# Full_Sonar_v1_opt_corrected_external_clo.net
KiCad netlist of a schematic drawn in EAGLE
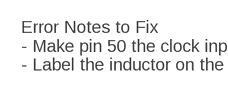
[diagram p0: schematic, sheet 1, part 1 of 2]
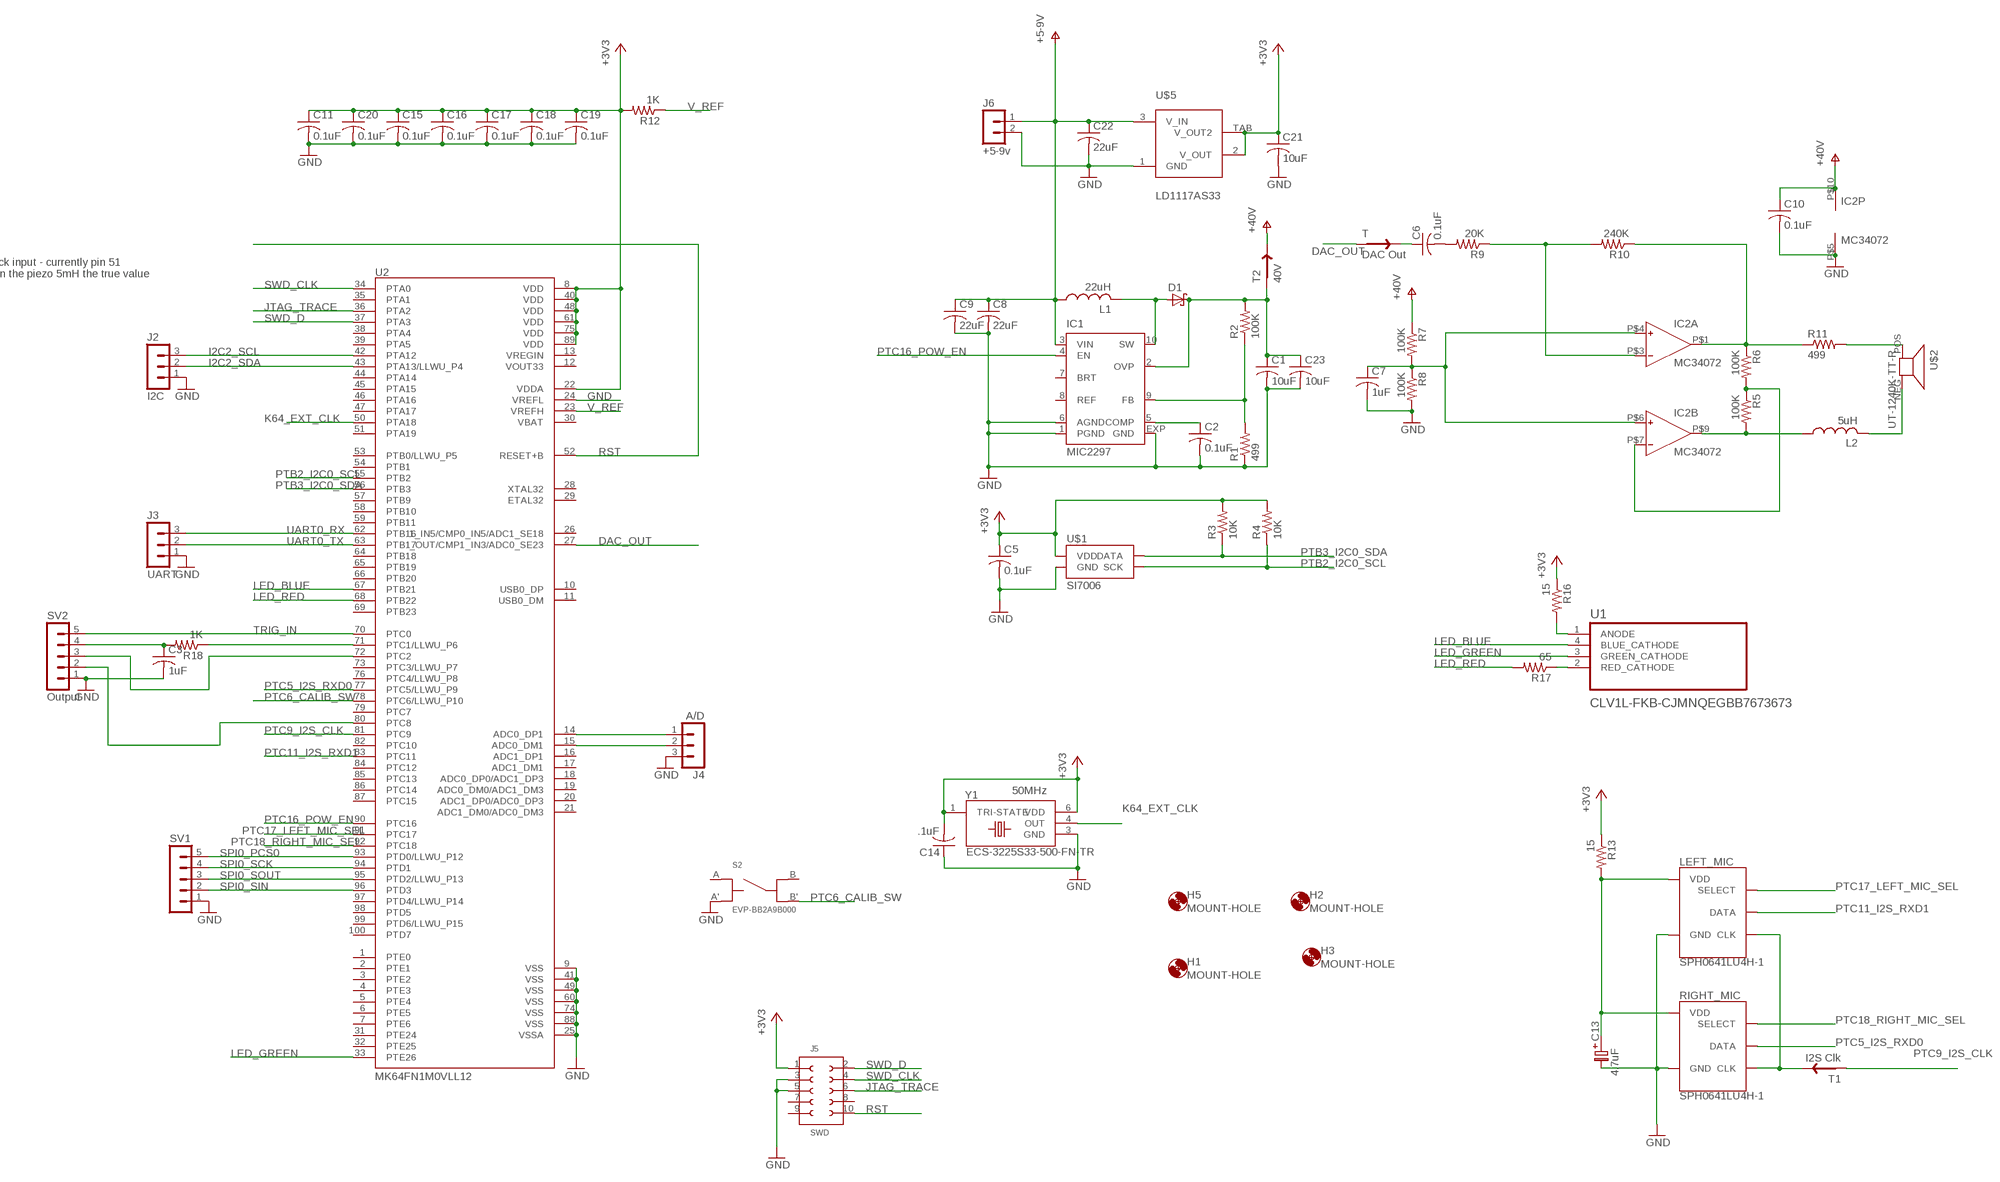
[diagram p1: schematic, sheet 1, part 2 of 2]

(export (version "E")
  (design (tool "Eeschema 10.0.6"))
  (components
    (comp (ref "C1")
      (value "10uF")
      (footprint "eagle-import:C1206")
      (libsource (lib "eagle-import") (part "C-USC1206"))
    )
    (comp (ref "C2")
      (value "0.1uF")
      (footprint "eagle-import:C0603")
      (libsource (lib "eagle-import") (part "C-USC0603"))
    )
    (comp (ref "C3")
      (value "1uF")
      (footprint "eagle-import:C0603")
      (libsource (lib "eagle-import") (part "C-USC0603"))
    )
    (comp (ref "C5")
      (value "0.1uF")
      (footprint "eagle-import:C0603")
      (libsource (lib "eagle-import") (part "C-USC0603"))
    )
    (comp (ref "C6")
      (value "0.1uF")
      (footprint "eagle-import:C0603")
      (libsource (lib "eagle-import") (part "C-USC0603"))
    )
    (comp (ref "C7")
      (value "1uF")
      (footprint "eagle-import:C0603")
      (libsource (lib "eagle-import") (part "C-USC0603"))
    )
    (comp (ref "C8")
      (value "22uF")
      (footprint "eagle-import:C0805")
      (libsource (lib "eagle-import") (part "C-USC0805"))
    )
    (comp (ref "C9")
      (value "22uF")
      (footprint "eagle-import:C0805")
      (libsource (lib "eagle-import") (part "C-USC0805"))
    )
    (comp (ref "C10")
      (value "0.1uF")
      (footprint "eagle-import:C0603")
      (libsource (lib "eagle-import") (part "C-USC0603"))
    )
    (comp (ref "C11")
      (value "0.1uF")
      (footprint "eagle-import:C0603")
      (libsource (lib "eagle-import") (part "C-USC0603"))
    )
    (comp (ref "C13")
      (value "4.7uF")
      (footprint "eagle-import:TE-A-3216")
      (libsource (lib "eagle-import") (part "CPOLA"))
    )
    (comp (ref "C14")
      (value ".1uF")
      (footprint "eagle-import:C0603")
      (libsource (lib "eagle-import") (part "C-USC0603"))
    )
    (comp (ref "C15")
      (value "0.1uF")
      (footprint "eagle-import:C0603K")
      (libsource (lib "eagle-import") (part "C-USC0603K"))
    )
    (comp (ref "C16")
      (value "0.1uF")
      (footprint "eagle-import:C0603")
      (libsource (lib "eagle-import") (part "C-USC0603"))
    )
    (comp (ref "C17")
      (value "0.1uF")
      (footprint "eagle-import:C0603")
      (libsource (lib "eagle-import") (part "C-USC0603"))
    )
    (comp (ref "C18")
      (value "0.1uF")
      (footprint "eagle-import:C0603")
      (libsource (lib "eagle-import") (part "C-USC0603"))
    )
    (comp (ref "C19")
      (value "0.1uF")
      (footprint "eagle-import:C0603")
      (libsource (lib "eagle-import") (part "C-USC0603"))
    )
    (comp (ref "C20")
      (value "0.1uF")
      (footprint "eagle-import:C0603K")
      (libsource (lib "eagle-import") (part "C-USC0603K"))
    )
    (comp (ref "C21")
      (value "10uF")
      (footprint "eagle-import:C0603")
      (libsource (lib "eagle-import") (part "C-USC0603"))
    )
    (comp (ref "C22")
      (value "22uF")
      (footprint "eagle-import:C0805")
      (libsource (lib "eagle-import") (part "C-USC0805"))
    )
    (comp (ref "C23")
      (value "10uF")
      (footprint "eagle-import:C1206")
      (libsource (lib "eagle-import") (part "C-USC1206"))
    )
    (comp (ref "D1")
      (value "DIODE_SCHOTTKYMICROSMP")
      (footprint "eagle-import:DIODE_SCHOTTKY_MICROSMP")
      (libsource (lib "eagle-import") (part "DIODE_SCHOTTKYMICROSMP"))
    )
    (comp (ref "H1")
      (value "MOUNT-HOLE")
      (footprint "eagle-import:SCREWHOLE2-56")
      (libsource (lib "eagle-import") (part "MOUNT-HOLE"))
    )
    (comp (ref "H2")
      (value "MOUNT-HOLE")
      (footprint "eagle-import:SCREWHOLE2-56")
      (libsource (lib "eagle-import") (part "MOUNT-HOLE"))
    )
    (comp (ref "H3")
      (value "MOUNT-HOLE")
      (footprint "eagle-import:SCREWHOLE2-56")
      (libsource (lib "eagle-import") (part "MOUNT-HOLE"))
    )
    (comp (ref "H5")
      (value "MOUNT-HOLE")
      (footprint "eagle-import:SCREWHOLE2-56")
      (libsource (lib "eagle-import") (part "MOUNT-HOLE"))
    )
    (comp (ref "IC1")
      (value "MIC2297")
      (footprint "eagle-import:MLF10")
      (fields (field (name "MPN") "MIC2297-38YML TR"))
      (libsource (lib "eagle-import") (part "MIC2297"))
    )
    (comp (ref "IC2")
      (value "MC34072")
      (footprint "eagle-import:WQFN10")
      (libsource (lib "eagle-import") (part "MC34072"))
    )
    (comp (ref "J2")
      (value "I2C")
      (footprint "eagle-import:MA03-1")
      (libsource (lib "eagle-import") (part "MA03-1"))
    )
    (comp (ref "J3")
      (value "UART")
      (footprint "eagle-import:MA03-1")
      (libsource (lib "eagle-import") (part "MA03-1"))
    )
    (comp (ref "J4")
      (value "A/D")
      (footprint "eagle-import:MA03-1")
      (libsource (lib "eagle-import") (part "MA03-1"))
    )
    (comp (ref "J5")
      (value "SWD")
      (footprint "eagle-import:62201021121")
      (fields (field (name "MF") "Würth Elektronik") (field (name "MP") "62201021121"))
      (libsource (lib "eagle-import") (part "62201021121"))
    )
    (comp (ref "J6")
      (value "+5-9v")
      (footprint "eagle-import:MA02-1")
      (libsource (lib "eagle-import") (part "MA02-1"))
    )
    (comp (ref "L1")
      (value "22uH")
      (footprint "eagle-import:INDUCTOR_BOURNS_SRN3012TA")
      (libsource (lib "eagle-import") (part "INDUCTOR7"))
    )
    (comp (ref "L2")
      (value "5uH")
      (footprint "eagle-import:INDUCTOR_BOURNS_SDR0503")
      (libsource (lib "eagle-import") (part "INDUCTOR"))
    )
    (comp (ref "LEFT_MIC")
      (value "SPH0641LU4H-1")
      (footprint "eagle-import:SPH0641LU4H-1")
      (libsource (lib "eagle-import") (part "SPH0641LU4H-1"))
    )
    (comp (ref "R1")
      (value "499")
      (footprint "eagle-import:R0603")
      (libsource (lib "eagle-import") (part "R-US_R0603"))
    )
    (comp (ref "R2")
      (value "100K")
      (footprint "eagle-import:R0603")
      (libsource (lib "eagle-import") (part "R-US_R0603"))
    )
    (comp (ref "R3")
      (value "10K")
      (footprint "eagle-import:R0603")
      (libsource (lib "eagle-import") (part "R-US_R0603"))
    )
    (comp (ref "R4")
      (value "10K")
      (footprint "eagle-import:R0603")
      (libsource (lib "eagle-import") (part "R-US_R0603"))
    )
    (comp (ref "R5")
      (value "100K")
      (footprint "eagle-import:R0603")
      (libsource (lib "eagle-import") (part "R-US_R0603"))
    )
    (comp (ref "R6")
      (value "100K")
      (footprint "eagle-import:R0603")
      (libsource (lib "eagle-import") (part "R-US_R0603"))
    )
    (comp (ref "R7")
      (value "100K")
      (footprint "eagle-import:R0603")
      (libsource (lib "eagle-import") (part "R-US_R0603"))
    )
    (comp (ref "R8")
      (value "100K")
      (footprint "eagle-import:R0603")
      (libsource (lib "eagle-import") (part "R-US_R0603"))
    )
    (comp (ref "R9")
      (value "20K")
      (footprint "eagle-import:R0603")
      (libsource (lib "eagle-import") (part "R-US_R0603"))
    )
    (comp (ref "R10")
      (value "240K")
      (footprint "eagle-import:R0603")
      (libsource (lib "eagle-import") (part "R-US_R0603"))
    )
    (comp (ref "R11")
      (value "499")
      (footprint "eagle-import:R0603")
      (libsource (lib "eagle-import") (part "R-US_R0603"))
    )
    (comp (ref "R12")
      (value "1K")
      (footprint "eagle-import:R0603")
      (libsource (lib "eagle-import") (part "R-US_R0603"))
    )
    (comp (ref "R13")
      (value "15")
      (footprint "eagle-import:R0603")
      (libsource (lib "eagle-import") (part "R-US_R0603"))
    )
    (comp (ref "R16")
      (value "15")
      (footprint "eagle-import:R0603")
      (libsource (lib "eagle-import") (part "R-US_R0603"))
    )
    (comp (ref "R17")
      (value "65")
      (footprint "eagle-import:R0603")
      (libsource (lib "eagle-import") (part "R-US_R0603"))
    )
    (comp (ref "R18")
      (value "1K")
      (footprint "eagle-import:R0603")
      (libsource (lib "eagle-import") (part "R-US_R0603"))
    )
    (comp (ref "RIGHT_MIC")
      (value "SPH0641LU4H-1")
      (footprint "eagle-import:SPH0641LU4H-1")
      (libsource (lib "eagle-import") (part "SPH0641LU4H-1"))
    )
    (comp (ref "S2")
      (value "EVP-BB2A9B000")
      (footprint "eagle-import:SW_EVP-BB2A9B000")
      (fields (field (name "MF") "Panasonic Electronic"))
      (libsource (lib "eagle-import") (part "EVP-BB2A9B000"))
    )
    (comp (ref "SV1")
      (value "MA05-1")
      (footprint "eagle-import:MA05-1")
      (libsource (lib "eagle-import") (part "MA05-1"))
    )
    (comp (ref "SV2")
      (value "Output")
      (footprint "eagle-import:MA05-1")
      (libsource (lib "eagle-import") (part "MA05-1"))
    )
    (comp (ref "T")
      (value "DAC Out")
      (footprint "eagle-import:TESTPAD")
      (libsource (lib "eagle-import") (part "TESTPAD{dblquote}{dblquote}"))
    )
    (comp (ref "T1")
      (value "I2S Clk")
      (footprint "eagle-import:TESTPAD")
      (libsource (lib "eagle-import") (part "TESTPAD{dblquote}{dblquote}"))
    )
    (comp (ref "T2")
      (value "40V")
      (footprint "eagle-import:TESTPAD")
      (libsource (lib "eagle-import") (part "TESTPAD{dblquote}{dblquote}"))
    )
    (comp (ref "U$1")
      (value "SI7006")
      (footprint "eagle-import:SI7006")
      (libsource (lib "eagle-import") (part "SI7006"))
    )
    (comp (ref "U$2")
      (value "UT-1240K-TT-R")
      (footprint "eagle-import:UT-1240K-TT-R")
      (libsource (lib "eagle-import") (part "UT-1240K-TT-R"))
    )
    (comp (ref "U$5")
      (value "LD1117AS33")
      (footprint "eagle-import:SOT223")
      (fields (field (name "MF") "STMicroelectronics"))
      (libsource (lib "eagle-import") (part "LD1117AS33"))
    )
    (comp (ref "U1")
      (value "CLV1L-FKB-CJMNQEGBB7673673")
      (footprint "eagle-import:SOJ150P350X372-4N")
      (fields (field (name "MF") "Cree"))
      (libsource (lib "eagle-import") (part "CLV1L-FKB-CJMNQEGBB7673673"))
    )
    (comp (ref "U2")
      (value "MK64FN1M0VLL12")
      (footprint "eagle-import:QFP50P1600X1600X170-100N")
      (fields (field (name "MF") "NXP Semiconductors"))
      (libsource (lib "eagle-import") (part "MK64FN1M0VLL12"))
    )
    (comp (ref "Y1")
      (value "ECS-3225S33-500-FN-TR")
      (footprint "eagle-import:XTAL_ECS-3225S18-050-EN-TR")
      (fields (field (name "DIGI-KEY_PART_NUMBER") "XC2226CT-ND") (field (name "MF") "ECS International"))
      (libsource (lib "eagle-import") (part "ECS-3225S33-500-FN-TR"))
    )
  )
  (nets
    (net (code "1") (name "+3V3") (class "Default")
      (node (ref "C11") (pin "1") (pinfunction "1_1") (pintype "passive"))
      (node (ref "C14") (pin "2") (pinfunction "2_2") (pintype "passive"))
      (node (ref "C15") (pin "1") (pinfunction "1_1") (pintype "passive"))
      (node (ref "C16") (pin "1") (pinfunction "1_1") (pintype "passive"))
      (node (ref "C17") (pin "1") (pinfunction "1_1") (pintype "passive"))
      (node (ref "C18") (pin "1") (pinfunction "1_1") (pintype "passive"))
      (node (ref "C19") (pin "1") (pinfunction "1_1") (pintype "passive"))
      (node (ref "C20") (pin "1") (pinfunction "1_1") (pintype "passive"))
      (node (ref "C21") (pin "1") (pinfunction "1_1") (pintype "passive"))
      (node (ref "C5") (pin "1") (pinfunction "1_1") (pintype "passive"))
      (node (ref "J5") (pin "1") (pinfunction "1_1") (pintype "passive"))
      (node (ref "R12") (pin "2") (pinfunction "2_2") (pintype "passive"))
      (node (ref "R13") (pin "1") (pinfunction "1_1") (pintype "passive"))
      (node (ref "R16") (pin "1") (pinfunction "1_1") (pintype "passive"))
      (node (ref "R3") (pin "2") (pinfunction "2_2") (pintype "passive"))
      (node (ref "R4") (pin "2") (pinfunction "2_2") (pintype "passive"))
      (node (ref "U$1") (pin "VDD") (pinfunction "VDD_VDD") (pintype "power_in"))
      (node (ref "U$5") (pin "2") (pinfunction "V_OUT_2") (pintype "bidirectional"))
      (node (ref "U$5") (pin "TAB") (pinfunction "V_OUT2_TAB") (pintype "bidirectional"))
      (node (ref "U2") (pin "22") (pinfunction "VDDA_22") (pintype "power_in"))
      (node (ref "U2") (pin "40") (pinfunction "VDD_40") (pintype "power_in"))
      (node (ref "U2") (pin "48") (pinfunction "VDD_48") (pintype "power_in"))
      (node (ref "U2") (pin "61") (pinfunction "VDD_61") (pintype "power_in"))
      (node (ref "U2") (pin "75") (pinfunction "VDD_75") (pintype "power_in"))
      (node (ref "U2") (pin "8") (pinfunction "VDD_8") (pintype "power_in"))
      (node (ref "U2") (pin "89") (pinfunction "VDD_89") (pintype "power_in"))
      (node (ref "Y1") (pin "1") (pinfunction "TRI-STATE_1") (pintype "input"))
      (node (ref "Y1") (pin "6") (pinfunction "VDD_6") (pintype "power_in"))
    )
    (net (code "2") (name "+5-9V") (class "Default")
      (node (ref "C22") (pin "1") (pinfunction "1_1") (pintype "passive"))
      (node (ref "C8") (pin "1") (pinfunction "1_1") (pintype "passive"))
      (node (ref "C9") (pin "1") (pinfunction "1_1") (pintype "passive"))
      (node (ref "IC1") (pin "3") (pinfunction "VIN_3") (pintype "input"))
      (node (ref "J6") (pin "1") (pinfunction "1_1") (pintype "passive"))
      (node (ref "L1") (pin "P$1") (pinfunction "1_P$1") (pintype "passive"))
      (node (ref "U$5") (pin "3") (pinfunction "V_IN_3") (pintype "bidirectional"))
    )
    (net (code "3") (name "DAC_OUT") (class "Default")
      (node (ref "T") (pin "IN") (pinfunction "IN_IN") (pintype "passive"))
      (node (ref "U2") (pin "27") (pinfunction "_OUT/CMP1_IN3/ADC0_SE23_27") (pintype "bidirectional"))
    )
    (net (code "4") (name "GND") (class "Default")
      (node (ref "C1") (pin "2") (pinfunction "2_2") (pintype "passive"))
      (node (ref "C10") (pin "2") (pinfunction "2_2") (pintype "passive"))
      (node (ref "C11") (pin "2") (pinfunction "2_2") (pintype "passive"))
      (node (ref "C13") (pin "-") (pinfunction "-_-") (pintype "passive"))
      (node (ref "C14") (pin "1") (pinfunction "1_1") (pintype "passive"))
      (node (ref "C15") (pin "2") (pinfunction "2_2") (pintype "passive"))
      (node (ref "C16") (pin "2") (pinfunction "2_2") (pintype "passive"))
      (node (ref "C17") (pin "2") (pinfunction "2_2") (pintype "passive"))
      (node (ref "C18") (pin "2") (pinfunction "2_2") (pintype "passive"))
      (node (ref "C19") (pin "2") (pinfunction "2_2") (pintype "passive"))
      (node (ref "C2") (pin "2") (pinfunction "2_2") (pintype "passive"))
      (node (ref "C20") (pin "2") (pinfunction "2_2") (pintype "passive"))
      (node (ref "C21") (pin "2") (pinfunction "2_2") (pintype "passive"))
      (node (ref "C22") (pin "2") (pinfunction "2_2") (pintype "passive"))
      (node (ref "C23") (pin "2") (pinfunction "2_2") (pintype "passive"))
      (node (ref "C3") (pin "2") (pinfunction "2_2") (pintype "passive"))
      (node (ref "C5") (pin "2") (pinfunction "2_2") (pintype "passive"))
      (node (ref "C7") (pin "2") (pinfunction "2_2") (pintype "passive"))
      (node (ref "C8") (pin "2") (pinfunction "2_2") (pintype "passive"))
      (node (ref "C9") (pin "2") (pinfunction "2_2") (pintype "passive"))
      (node (ref "IC1") (pin "1") (pinfunction "PGND_1") (pintype "input"))
      (node (ref "IC1") (pin "6") (pinfunction "AGND_6") (pintype "input"))
      (node (ref "IC1") (pin "EXP") (pinfunction "GND_EXP") (pintype "input"))
      (node (ref "IC2") (pin "P$5") (pinfunction "V-_P$5") (pintype "power_in"))
      (node (ref "J2") (pin "1") (pinfunction "1_1") (pintype "passive"))
      (node (ref "J3") (pin "1") (pinfunction "1_1") (pintype "passive"))
      (node (ref "J4") (pin "3") (pinfunction "3_3") (pintype "passive"))
      (node (ref "J5") (pin "3") (pinfunction "2_3") (pintype "passive"))
      (node (ref "J5") (pin "5") (pinfunction "3_5") (pintype "passive"))
      (node (ref "J6") (pin "2") (pinfunction "2_2") (pintype "passive"))
      (node (ref "LEFT_MIC") (pin "3") (pinfunction "GND_3") (pintype "bidirectional"))
      (node (ref "R1") (pin "1") (pinfunction "1_1") (pintype "passive"))
      (node (ref "R8") (pin "2") (pinfunction "2_2") (pintype "passive"))
      (node (ref "RIGHT_MIC") (pin "3") (pinfunction "GND_3") (pintype "bidirectional"))
      (node (ref "S2") (pin "A'") (pinfunction "A'_A'") (pintype "passive"))
      (node (ref "SV1") (pin "1") (pinfunction "1_1") (pintype "passive"))
      (node (ref "SV2") (pin "1") (pinfunction "1_1") (pintype "passive"))
      (node (ref "U$1") (pin "GND") (pinfunction "GND_GND") (pintype "power_in"))
      (node (ref "U$5") (pin "1") (pinfunction "GND_1") (pintype "bidirectional"))
      (node (ref "U2") (pin "24") (pinfunction "VREFL_24") (pintype "power_in"))
      (node (ref "U2") (pin "25") (pinfunction "VSSA_25") (pintype "power_in"))
      (node (ref "U2") (pin "41") (pinfunction "VSS_41") (pintype "power_in"))
      (node (ref "U2") (pin "49") (pinfunction "VSS_49") (pintype "power_in"))
      (node (ref "U2") (pin "60") (pinfunction "VSS_60") (pintype "power_in"))
      (node (ref "U2") (pin "74") (pinfunction "VSS_74") (pintype "power_in"))
      (node (ref "U2") (pin "88") (pinfunction "VSS_88") (pintype "power_in"))
      (node (ref "U2") (pin "9") (pinfunction "VSS_9") (pintype "power_in"))
      (node (ref "Y1") (pin "3") (pinfunction "GND_3") (pintype "power_in"))
    )
    (net (code "5") (name "I2C2_SCL") (class "Default")
      (node (ref "J2") (pin "3") (pinfunction "3_3") (pintype "passive"))
      (node (ref "U2") (pin "42") (pinfunction "PTA12_42") (pintype "bidirectional"))
    )
    (net (code "6") (name "I2C2_SDA") (class "Default")
      (node (ref "J2") (pin "2") (pinfunction "2_2") (pintype "passive"))
      (node (ref "U2") (pin "43") (pinfunction "PTA13/LLWU_P4_43") (pintype "bidirectional"))
    )
    (net (code "7") (name "JTAG_TRACE") (class "Default")
      (node (ref "J5") (pin "6") (pinfunction "8_6") (pintype "passive"))
      (node (ref "U2") (pin "36") (pinfunction "PTA2_36") (pintype "bidirectional"))
    )
    (net (code "8") (name "K64_EXT_CLK") (class "Default")
      (node (ref "U2") (pin "50") (pinfunction "PTA18_50") (pintype "bidirectional"))
      (node (ref "Y1") (pin "4") (pinfunction "OUT_4") (pintype "output"))
    )
    (net (code "9") (name "LED_BLUE") (class "Default")
      (node (ref "U1") (pin "4") (pinfunction "BLUE_CATHODE_4") (pintype "bidirectional"))
      (node (ref "U2") (pin "67") (pinfunction "PTB21_67") (pintype "bidirectional"))
    )
    (net (code "10") (name "LED_GREEN") (class "Default")
      (node (ref "U1") (pin "3") (pinfunction "GREEN_CATHODE_3") (pintype "bidirectional"))
      (node (ref "U2") (pin "33") (pinfunction "PTE26_33") (pintype "bidirectional"))
    )
    (net (code "11") (name "LED_RED") (class "Default")
      (node (ref "R17") (pin "2") (pinfunction "2_2") (pintype "passive"))
      (node (ref "U2") (pin "68") (pinfunction "PTB22_68") (pintype "bidirectional"))
    )
    (net (code "12") (name "Net-(C3-Pad1)") (class "Default")
      (node (ref "C3") (pin "1") (pinfunction "1_1") (pintype "passive"))
      (node (ref "R18") (pin "2") (pinfunction "2_2") (pintype "passive"))
      (node (ref "SV2") (pin "4") (pinfunction "4_4") (pintype "passive"))
    )
    (net (code "13") (name "Net-(C6-Pad1)") (class "Default")
      (node (ref "C6") (pin "1") (pinfunction "1_1") (pintype "passive"))
      (node (ref "T") (pin "OUT") (pinfunction "OUT_OUT") (pintype "passive"))
    )
    (net (code "14") (name "Net-(C6-Pad2)") (class "Default")
      (node (ref "C6") (pin "2") (pinfunction "2_2") (pintype "passive"))
      (node (ref "R9") (pin "2") (pinfunction "2_2") (pintype "passive"))
    )
    (net (code "15") (name "Net-(IC1-COMP)") (class "Default")
      (node (ref "C2") (pin "1") (pinfunction "1_1") (pintype "passive"))
      (node (ref "IC1") (pin "5") (pinfunction "COMP_5") (pintype "passive"))
    )
    (net (code "16") (name "Net-(IC1-FB)") (class "Default")
      (node (ref "IC1") (pin "9") (pinfunction "FB_9") (pintype "input"))
      (node (ref "R1") (pin "2") (pinfunction "2_2") (pintype "passive"))
      (node (ref "R2") (pin "1") (pinfunction "1_1") (pintype "passive"))
    )
    (net (code "17") (name "Net-(IC1-OVP)") (class "Default")
      (node (ref "C1") (pin "1") (pinfunction "1_1") (pintype "passive"))
      (node (ref "C23") (pin "1") (pinfunction "1_1") (pintype "passive"))
      (node (ref "D1") (pin "C") (pinfunction "C_C") (pintype "passive"))
      (node (ref "IC1") (pin "2") (pinfunction "OVP_2") (pintype "input"))
      (node (ref "R2") (pin "2") (pinfunction "2_2") (pintype "passive"))
      (node (ref "T2") (pin "IN") (pinfunction "IN_IN") (pintype "passive"))
    )
    (net (code "18") (name "Net-(IC1-SW)") (class "Default")
      (node (ref "D1") (pin "A") (pinfunction "A_A") (pintype "passive"))
      (node (ref "IC1") (pin "10") (pinfunction "SW_10") (pintype "open_collector"))
      (node (ref "L1") (pin "P$2") (pinfunction "2_P$2") (pintype "passive"))
    )
    (net (code "19") (name "Net-(IC2A-IN+)") (class "Default")
      (node (ref "C7") (pin "1") (pinfunction "1_1") (pintype "passive"))
      (node (ref "IC2") (pin "P$4") (pinfunction "IN+_P$4") (pintype "input"))
      (node (ref "IC2") (pin "P$6") (pinfunction "IN+_P$6") (pintype "input"))
      (node (ref "R7") (pin "2") (pinfunction "2_2") (pintype "passive"))
      (node (ref "R8") (pin "1") (pinfunction "1_1") (pintype "passive"))
    )
    (net (code "20") (name "Net-(IC2A-IN-)") (class "Default")
      (node (ref "IC2") (pin "P$3") (pinfunction "IN-_P$3") (pintype "input"))
      (node (ref "R10") (pin "2") (pinfunction "2_2") (pintype "passive"))
      (node (ref "R9") (pin "1") (pinfunction "1_1") (pintype "passive"))
    )
    (net (code "21") (name "Net-(IC2A-OUT)") (class "Default")
      (node (ref "IC2") (pin "P$1") (pinfunction "OUT_P$1") (pintype "output"))
      (node (ref "R10") (pin "1") (pinfunction "1_1") (pintype "passive"))
      (node (ref "R11") (pin "1") (pinfunction "1_1") (pintype "passive"))
      (node (ref "R6") (pin "1") (pinfunction "1_1") (pintype "passive"))
    )
    (net (code "22") (name "Net-(IC2B-IN-)") (class "Default")
      (node (ref "IC2") (pin "P$7") (pinfunction "IN-_P$7") (pintype "input"))
      (node (ref "R5") (pin "1") (pinfunction "1_1") (pintype "passive"))
      (node (ref "R6") (pin "2") (pinfunction "2_2") (pintype "passive"))
    )
    (net (code "23") (name "Net-(IC2B-OUT)") (class "Default")
      (node (ref "IC2") (pin "P$9") (pinfunction "OUT_P$9") (pintype "output"))
      (node (ref "L2") (pin "1") (pinfunction "1_1") (pintype "passive"))
      (node (ref "R5") (pin "2") (pinfunction "2_2") (pintype "passive"))
    )
    (net (code "24") (name "Net-(L2-Pad2)") (class "Default")
      (node (ref "L2") (pin "2") (pinfunction "2_2") (pintype "passive"))
      (node (ref "U$2") (pin "NEG") (pinfunction "NEG_NEG") (pintype "passive"))
    )
    (net (code "25") (name "Net-(LEFT_MIC-CLK)") (class "Default")
      (node (ref "LEFT_MIC") (pin "4") (pinfunction "CLK_4") (pintype "bidirectional"))
      (node (ref "RIGHT_MIC") (pin "4") (pinfunction "CLK_4") (pintype "bidirectional"))
      (node (ref "T1") (pin "OUT") (pinfunction "OUT_OUT") (pintype "passive"))
    )
    (net (code "26") (name "Net-(LEFT_MIC-VDD)") (class "Default")
      (node (ref "C13") (pin "+") (pinfunction "+_+") (pintype "passive"))
      (node (ref "LEFT_MIC") (pin "5") (pinfunction "VDD_5") (pintype "bidirectional"))
      (node (ref "R13") (pin "2") (pinfunction "2_2") (pintype "passive"))
      (node (ref "RIGHT_MIC") (pin "5") (pinfunction "VDD_5") (pintype "bidirectional"))
    )
    (net (code "27") (name "Net-(R11-Pad2)") (class "Default")
      (node (ref "R11") (pin "2") (pinfunction "2_2") (pintype "passive"))
      (node (ref "U$2") (pin "POS") (pinfunction "POS_POS") (pintype "passive"))
    )
    (net (code "28") (name "Net-(U1-ANODE)") (class "Default")
      (node (ref "R16") (pin "2") (pinfunction "2_2") (pintype "passive"))
      (node (ref "U1") (pin "1") (pinfunction "ANODE_1") (pintype "bidirectional"))
    )
    (net (code "29") (name "Net-(U1-RED_CATHODE)") (class "Default")
      (node (ref "R17") (pin "1") (pinfunction "1_1") (pintype "passive"))
      (node (ref "U1") (pin "2") (pinfunction "RED_CATHODE_2") (pintype "bidirectional"))
    )
    (net (code "30") (name "Net-(U2-ADC0_DM1)") (class "Default")
      (node (ref "J4") (pin "2") (pinfunction "2_2") (pintype "passive"))
      (node (ref "U2") (pin "15") (pinfunction "ADC0_DM1_15") (pintype "bidirectional"))
    )
    (net (code "31") (name "Net-(U2-ADC0_DP1)") (class "Default")
      (node (ref "J4") (pin "1") (pinfunction "1_1") (pintype "passive"))
      (node (ref "U2") (pin "14") (pinfunction "ADC0_DP1_14") (pintype "bidirectional"))
    )
    (net (code "32") (name "Net-(U2-PTC1{slash}LLWU_P6)") (class "Default")
      (node (ref "R18") (pin "1") (pinfunction "1_1") (pintype "passive"))
      (node (ref "U2") (pin "71") (pinfunction "PTC1/LLWU_P6_71") (pintype "bidirectional"))
    )
    (net (code "33") (name "Net-(U2-PTC2)") (class "Default")
      (node (ref "SV2") (pin "3") (pinfunction "3_3") (pintype "passive"))
      (node (ref "U2") (pin "72") (pinfunction "PTC2_72") (pintype "bidirectional"))
    )
    (net (code "34") (name "Net-(U2-PTC8)") (class "Default")
      (node (ref "SV2") (pin "2") (pinfunction "2_2") (pintype "passive"))
      (node (ref "U2") (pin "80") (pinfunction "PTC8_80") (pintype "bidirectional"))
    )
    (net (code "35") (name "PTB2_I2C0_SCL") (class "Default")
      (node (ref "R4") (pin "1") (pinfunction "1_1") (pintype "passive"))
      (node (ref "U$1") (pin "SCK") (pinfunction "SCK_SCK") (pintype "input"))
      (node (ref "U2") (pin "55") (pinfunction "PTB2_55") (pintype "bidirectional"))
    )
    (net (code "36") (name "PTB3_I2C0_SDA") (class "Default")
      (node (ref "R3") (pin "1") (pinfunction "1_1") (pintype "passive"))
      (node (ref "U$1") (pin "DATA") (pinfunction "DATA_DATA") (pintype "bidirectional"))
      (node (ref "U2") (pin "56") (pinfunction "PTB3_56") (pintype "bidirectional"))
    )
    (net (code "37") (name "PTC5_I2S_RXD0") (class "Default")
      (node (ref "RIGHT_MIC") (pin "1") (pinfunction "DATA_1") (pintype "bidirectional"))
      (node (ref "U2") (pin "77") (pinfunction "PTC5/LLWU_P9_77") (pintype "bidirectional"))
    )
    (net (code "38") (name "PTC6_CALIB_SW") (class "Default")
      (node (ref "S2") (pin "B'") (pinfunction "B'_B'") (pintype "passive"))
      (node (ref "U2") (pin "78") (pinfunction "PTC6/LLWU_P10_78") (pintype "bidirectional"))
    )
    (net (code "39") (name "PTC9_I2S_CLK") (class "Default")
      (node (ref "T1") (pin "IN") (pinfunction "IN_IN") (pintype "passive"))
      (node (ref "U2") (pin "81") (pinfunction "PTC9_81") (pintype "bidirectional"))
    )
    (net (code "40") (name "PTC11_I2S_RXD1") (class "Default")
      (node (ref "LEFT_MIC") (pin "1") (pinfunction "DATA_1") (pintype "bidirectional"))
      (node (ref "U2") (pin "83") (pinfunction "PTC11_83") (pintype "bidirectional"))
    )
    (net (code "41") (name "PTC16_POW_EN") (class "Default")
      (node (ref "IC1") (pin "4") (pinfunction "EN_4") (pintype "input"))
      (node (ref "U2") (pin "90") (pinfunction "PTC16_90") (pintype "bidirectional"))
    )
    (net (code "42") (name "PTC17_LEFT_MIC_SEL") (class "Default")
      (node (ref "LEFT_MIC") (pin "2") (pinfunction "SELECT_2") (pintype "bidirectional"))
      (node (ref "U2") (pin "91") (pinfunction "PTC17_91") (pintype "bidirectional"))
    )
    (net (code "43") (name "PTC18_RIGHT_MIC_SEL") (class "Default")
      (node (ref "RIGHT_MIC") (pin "2") (pinfunction "SELECT_2") (pintype "bidirectional"))
      (node (ref "U2") (pin "92") (pinfunction "PTC18_92") (pintype "bidirectional"))
    )
    (net (code "44") (name "RST") (class "Default")
      (node (ref "J5") (pin "10") (pinfunction "6_10") (pintype "passive"))
      (node (ref "U2") (pin "52") (pinfunction "RESET+B_52") (pintype "bidirectional"))
    )
    (net (code "45") (name "SPI0_PCS0") (class "Default")
      (node (ref "SV1") (pin "5") (pinfunction "5_5") (pintype "passive"))
      (node (ref "U2") (pin "93") (pinfunction "PTD0/LLWU_P12_93") (pintype "bidirectional"))
    )
    (net (code "46") (name "SPI0_SCK") (class "Default")
      (node (ref "SV1") (pin "4") (pinfunction "4_4") (pintype "passive"))
      (node (ref "U2") (pin "94") (pinfunction "PTD1_94") (pintype "bidirectional"))
    )
    (net (code "47") (name "SPI0_SIN") (class "Default")
      (node (ref "SV1") (pin "2") (pinfunction "2_2") (pintype "passive"))
      (node (ref "U2") (pin "96") (pinfunction "PTD3_96") (pintype "bidirectional"))
    )
    (net (code "48") (name "SPI0_SOUT") (class "Default")
      (node (ref "SV1") (pin "3") (pinfunction "3_3") (pintype "passive"))
      (node (ref "U2") (pin "95") (pinfunction "PTD2/LLWU_P13_95") (pintype "bidirectional"))
    )
    (net (code "49") (name "SWD_CLK") (class "Default")
      (node (ref "J5") (pin "4") (pinfunction "9_4") (pintype "passive"))
      (node (ref "U2") (pin "34") (pinfunction "PTA0_34") (pintype "bidirectional"))
    )
    (net (code "50") (name "SWD_D") (class "Default")
      (node (ref "J5") (pin "2") (pinfunction "10_2") (pintype "passive"))
      (node (ref "U2") (pin "37") (pinfunction "PTA3_37") (pintype "bidirectional"))
    )
    (net (code "51") (name "TRIG_IN") (class "Default")
      (node (ref "SV2") (pin "5") (pinfunction "5_5") (pintype "passive"))
      (node (ref "U2") (pin "70") (pinfunction "PTC0_70") (pintype "bidirectional"))
    )
    (net (code "52") (name "UART0_RX") (class "Default")
      (node (ref "J3") (pin "3") (pinfunction "3_3") (pintype "passive"))
      (node (ref "U2") (pin "62") (pinfunction "PTB16_62") (pintype "bidirectional"))
    )
    (net (code "53") (name "UART0_TX") (class "Default")
      (node (ref "J3") (pin "2") (pinfunction "2_2") (pintype "passive"))
      (node (ref "U2") (pin "63") (pinfunction "PTB17_63") (pintype "bidirectional"))
    )
    (net (code "54") (name "V+") (class "Default")
      (node (ref "C10") (pin "1") (pinfunction "1_1") (pintype "passive"))
      (node (ref "IC2") (pin "P$10") (pinfunction "V+_P$10") (pintype "power_in"))
      (node (ref "R7") (pin "1") (pinfunction "1_1") (pintype "passive"))
      (node (ref "T2") (pin "OUT") (pinfunction "OUT_OUT") (pintype "passive"))
    )
    (net (code "55") (name "VBAT") (class "Default")
      (node (ref "U2") (pin "30") (pinfunction "VBAT_30") (pintype "power_in"))
    )
    (net (code "56") (name "VOUT33") (class "Default")
      (node (ref "U2") (pin "12") (pinfunction "VOUT33_12") (pintype "power_in"))
    )
    (net (code "57") (name "VREGIN") (class "Default")
      (node (ref "U2") (pin "13") (pinfunction "VREGIN_13") (pintype "power_in"))
    )
    (net (code "58") (name "V_REF") (class "Default")
      (node (ref "R12") (pin "1") (pinfunction "1_1") (pintype "passive"))
      (node (ref "U2") (pin "23") (pinfunction "VREFH_23") (pintype "power_in"))
    )
    (net (code "59") (name "unconnected-(IC1-BRT-Pad7)") (class "Default")
      (node (ref "IC1") (pin "7") (pinfunction "BRT_7") (pintype "input"))
    )
    (net (code "60") (name "unconnected-(IC1-REF-Pad8)") (class "Default")
      (node (ref "IC1") (pin "8") (pinfunction "REF_8") (pintype "input"))
    )
    (net (code "61") (name "unconnected-(J5-4-Pad7)") (class "Default")
      (node (ref "J5") (pin "7") (pinfunction "4_7") (pintype "passive"))
    )
    (net (code "62") (name "unconnected-(J5-5-Pad9)") (class "Default")
      (node (ref "J5") (pin "9") (pinfunction "5_9") (pintype "passive"))
    )
    (net (code "63") (name "unconnected-(J5-7-Pad8)") (class "Default")
      (node (ref "J5") (pin "8") (pinfunction "7_8") (pintype "passive"))
    )
    (net (code "64") (name "unconnected-(S2-PadA)") (class "Default")
      (node (ref "S2") (pin "A") (pinfunction "A_A") (pintype "passive"))
    )
    (net (code "65") (name "unconnected-(S2-PadB)") (class "Default")
      (node (ref "S2") (pin "B") (pinfunction "B_B") (pintype "passive"))
    )
    (net (code "66") (name "unconnected-(U2-1_IN5{slash}CMP0_IN5{slash}ADC1_SE18-Pad26)") (class "Default")
      (node (ref "U2") (pin "26") (pinfunction "1_IN5/CMP0_IN5/ADC1_SE18_26") (pintype "bidirectional"))
    )
    (net (code "67") (name "unconnected-(U2-ADC0_DM0{slash}ADC1_DM3-Pad19)") (class "Default")
      (node (ref "U2") (pin "19") (pinfunction "ADC0_DM0/ADC1_DM3_19") (pintype "bidirectional"))
    )
    (net (code "68") (name "unconnected-(U2-ADC0_DP0{slash}ADC1_DP3-Pad18)") (class "Default")
      (node (ref "U2") (pin "18") (pinfunction "ADC0_DP0/ADC1_DP3_18") (pintype "bidirectional"))
    )
    (net (code "69") (name "unconnected-(U2-ADC1_DM0{slash}ADC0_DM3-Pad21)") (class "Default")
      (node (ref "U2") (pin "21") (pinfunction "ADC1_DM0/ADC0_DM3_21") (pintype "bidirectional"))
    )
    (net (code "70") (name "unconnected-(U2-ADC1_DM1-Pad17)") (class "Default")
      (node (ref "U2") (pin "17") (pinfunction "ADC1_DM1_17") (pintype "bidirectional"))
    )
    (net (code "71") (name "unconnected-(U2-ADC1_DP0{slash}ADC0_DP3-Pad20)") (class "Default")
      (node (ref "U2") (pin "20") (pinfunction "ADC1_DP0/ADC0_DP3_20") (pintype "bidirectional"))
    )
    (net (code "72") (name "unconnected-(U2-ADC1_DP1-Pad16)") (class "Default")
      (node (ref "U2") (pin "16") (pinfunction "ADC1_DP1_16") (pintype "bidirectional"))
    )
    (net (code "73") (name "unconnected-(U2-ETAL32-Pad29)") (class "Default")
      (node (ref "U2") (pin "29") (pinfunction "ETAL32_29") (pintype "bidirectional"))
    )
    (net (code "74") (name "unconnected-(U2-PTA1-Pad35)") (class "Default")
      (node (ref "U2") (pin "35") (pinfunction "PTA1_35") (pintype "bidirectional"))
    )
    (net (code "75") (name "unconnected-(U2-PTA4-Pad38)") (class "Default")
      (node (ref "U2") (pin "38") (pinfunction "PTA4_38") (pintype "bidirectional"))
    )
    (net (code "76") (name "unconnected-(U2-PTA5-Pad39)") (class "Default")
      (node (ref "U2") (pin "39") (pinfunction "PTA5_39") (pintype "bidirectional"))
    )
    (net (code "77") (name "unconnected-(U2-PTA14-Pad44)") (class "Default")
      (node (ref "U2") (pin "44") (pinfunction "PTA14_44") (pintype "bidirectional"))
    )
    (net (code "78") (name "unconnected-(U2-PTA15-Pad45)") (class "Default")
      (node (ref "U2") (pin "45") (pinfunction "PTA15_45") (pintype "bidirectional"))
    )
    (net (code "79") (name "unconnected-(U2-PTA16-Pad46)") (class "Default")
      (node (ref "U2") (pin "46") (pinfunction "PTA16_46") (pintype "bidirectional"))
    )
    (net (code "80") (name "unconnected-(U2-PTA17-Pad47)") (class "Default")
      (node (ref "U2") (pin "47") (pinfunction "PTA17_47") (pintype "bidirectional"))
    )
    (net (code "81") (name "unconnected-(U2-PTA19-Pad51)") (class "Default")
      (node (ref "U2") (pin "51") (pinfunction "PTA19_51") (pintype "bidirectional"))
    )
    (net (code "82") (name "unconnected-(U2-PTB0{slash}LLWU_P5-Pad53)") (class "Default")
      (node (ref "U2") (pin "53") (pinfunction "PTB0/LLWU_P5_53") (pintype "bidirectional"))
    )
    (net (code "83") (name "unconnected-(U2-PTB1-Pad54)") (class "Default")
      (node (ref "U2") (pin "54") (pinfunction "PTB1_54") (pintype "bidirectional"))
    )
    (net (code "84") (name "unconnected-(U2-PTB9-Pad57)") (class "Default")
      (node (ref "U2") (pin "57") (pinfunction "PTB9_57") (pintype "bidirectional"))
    )
    (net (code "85") (name "unconnected-(U2-PTB10-Pad58)") (class "Default")
      (node (ref "U2") (pin "58") (pinfunction "PTB10_58") (pintype "bidirectional"))
    )
    (net (code "86") (name "unconnected-(U2-PTB11-Pad59)") (class "Default")
      (node (ref "U2") (pin "59") (pinfunction "PTB11_59") (pintype "bidirectional"))
    )
    (net (code "87") (name "unconnected-(U2-PTB18-Pad64)") (class "Default")
      (node (ref "U2") (pin "64") (pinfunction "PTB18_64") (pintype "bidirectional"))
    )
    (net (code "88") (name "unconnected-(U2-PTB19-Pad65)") (class "Default")
      (node (ref "U2") (pin "65") (pinfunction "PTB19_65") (pintype "bidirectional"))
    )
    (net (code "89") (name "unconnected-(U2-PTB20-Pad66)") (class "Default")
      (node (ref "U2") (pin "66") (pinfunction "PTB20_66") (pintype "bidirectional"))
    )
    (net (code "90") (name "unconnected-(U2-PTB23-Pad69)") (class "Default")
      (node (ref "U2") (pin "69") (pinfunction "PTB23_69") (pintype "bidirectional"))
    )
    (net (code "91") (name "unconnected-(U2-PTC3{slash}LLWU_P7-Pad73)") (class "Default")
      (node (ref "U2") (pin "73") (pinfunction "PTC3/LLWU_P7_73") (pintype "bidirectional"))
    )
    (net (code "92") (name "unconnected-(U2-PTC4{slash}LLWU_P8-Pad76)") (class "Default")
      (node (ref "U2") (pin "76") (pinfunction "PTC4/LLWU_P8_76") (pintype "bidirectional"))
    )
    (net (code "93") (name "unconnected-(U2-PTC7-Pad79)") (class "Default")
      (node (ref "U2") (pin "79") (pinfunction "PTC7_79") (pintype "bidirectional"))
    )
    (net (code "94") (name "unconnected-(U2-PTC10-Pad82)") (class "Default")
      (node (ref "U2") (pin "82") (pinfunction "PTC10_82") (pintype "bidirectional"))
    )
    (net (code "95") (name "unconnected-(U2-PTC12-Pad84)") (class "Default")
      (node (ref "U2") (pin "84") (pinfunction "PTC12_84") (pintype "bidirectional"))
    )
    (net (code "96") (name "unconnected-(U2-PTC13-Pad85)") (class "Default")
      (node (ref "U2") (pin "85") (pinfunction "PTC13_85") (pintype "bidirectional"))
    )
    (net (code "97") (name "unconnected-(U2-PTC14-Pad86)") (class "Default")
      (node (ref "U2") (pin "86") (pinfunction "PTC14_86") (pintype "bidirectional"))
    )
    (net (code "98") (name "unconnected-(U2-PTC15-Pad87)") (class "Default")
      (node (ref "U2") (pin "87") (pinfunction "PTC15_87") (pintype "bidirectional"))
    )
    (net (code "99") (name "unconnected-(U2-PTD4{slash}LLWU_P14-Pad97)") (class "Default")
      (node (ref "U2") (pin "97") (pinfunction "PTD4/LLWU_P14_97") (pintype "bidirectional"))
    )
    (net (code "100") (name "unconnected-(U2-PTD5-Pad98)") (class "Default")
      (node (ref "U2") (pin "98") (pinfunction "PTD5_98") (pintype "bidirectional"))
    )
    (net (code "101") (name "unconnected-(U2-PTD6{slash}LLWU_P15-Pad99)") (class "Default")
      (node (ref "U2") (pin "99") (pinfunction "PTD6/LLWU_P15_99") (pintype "bidirectional"))
    )
    (net (code "102") (name "unconnected-(U2-PTD7-Pad100)") (class "Default")
      (node (ref "U2") (pin "100") (pinfunction "PTD7_100") (pintype "bidirectional"))
    )
    (net (code "103") (name "unconnected-(U2-PTE0-Pad1)") (class "Default")
      (node (ref "U2") (pin "1") (pinfunction "PTE0_1") (pintype "bidirectional"))
    )
    (net (code "104") (name "unconnected-(U2-PTE1-Pad2)") (class "Default")
      (node (ref "U2") (pin "2") (pinfunction "PTE1_2") (pintype "bidirectional"))
    )
    (net (code "105") (name "unconnected-(U2-PTE2-Pad3)") (class "Default")
      (node (ref "U2") (pin "3") (pinfunction "PTE2_3") (pintype "bidirectional"))
    )
    (net (code "106") (name "unconnected-(U2-PTE3-Pad4)") (class "Default")
      (node (ref "U2") (pin "4") (pinfunction "PTE3_4") (pintype "bidirectional"))
    )
    (net (code "107") (name "unconnected-(U2-PTE4-Pad5)") (class "Default")
      (node (ref "U2") (pin "5") (pinfunction "PTE4_5") (pintype "bidirectional"))
    )
    (net (code "108") (name "unconnected-(U2-PTE5-Pad6)") (class "Default")
      (node (ref "U2") (pin "6") (pinfunction "PTE5_6") (pintype "bidirectional"))
    )
    (net (code "109") (name "unconnected-(U2-PTE6-Pad7)") (class "Default")
      (node (ref "U2") (pin "7") (pinfunction "PTE6_7") (pintype "bidirectional"))
    )
    (net (code "110") (name "unconnected-(U2-PTE24-Pad31)") (class "Default")
      (node (ref "U2") (pin "31") (pinfunction "PTE24_31") (pintype "bidirectional"))
    )
    (net (code "111") (name "unconnected-(U2-PTE25-Pad32)") (class "Default")
      (node (ref "U2") (pin "32") (pinfunction "PTE25_32") (pintype "bidirectional"))
    )
    (net (code "112") (name "unconnected-(U2-USB0_DM-Pad11)") (class "Default")
      (node (ref "U2") (pin "11") (pinfunction "USB0_DM_11") (pintype "bidirectional"))
    )
    (net (code "113") (name "unconnected-(U2-USB0_DP-Pad10)") (class "Default")
      (node (ref "U2") (pin "10") (pinfunction "USB0_DP_10") (pintype "bidirectional"))
    )
    (net (code "114") (name "unconnected-(U2-XTAL32-Pad28)") (class "Default")
      (node (ref "U2") (pin "28") (pinfunction "XTAL32_28") (pintype "bidirectional"))
    )
  )
)
